# ADRF6510.net
KiCad netlist of a schematic drawn in Altium Designer
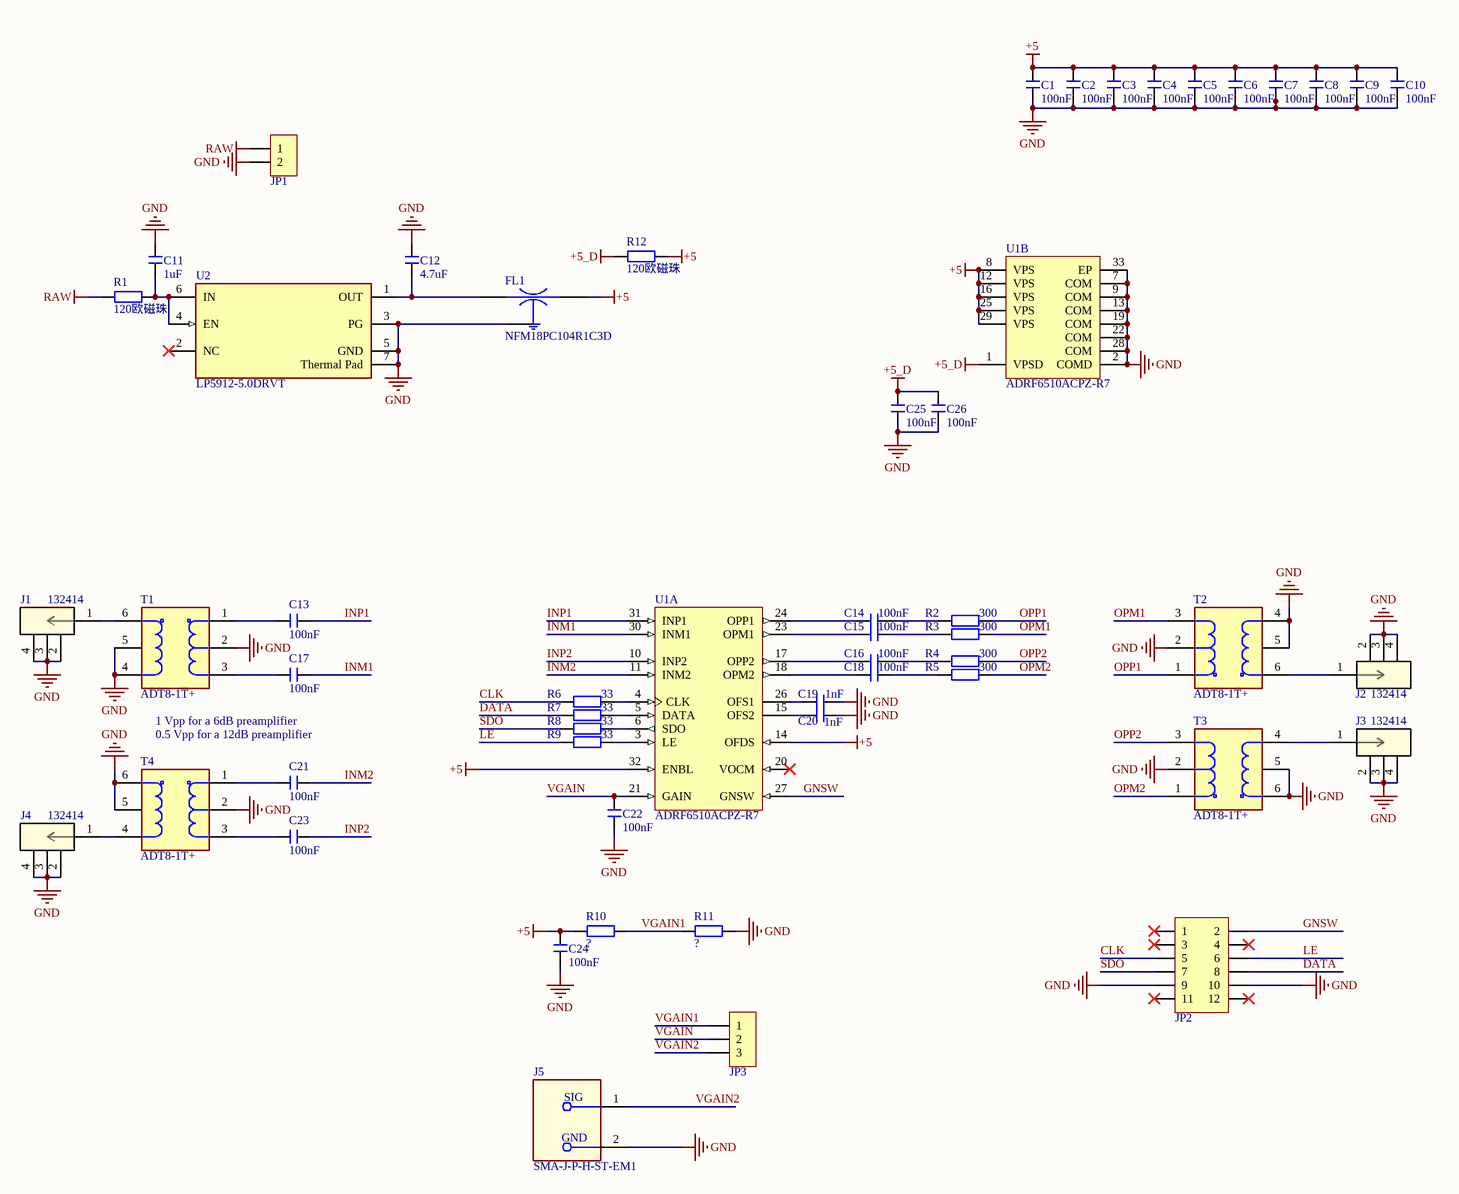
[diagram p0: ADRF6510.SchDoc]

(export (version "E")
  (design (tool "Eeschema 10.0.6"))
  (components
    (comp (ref "C1")
      (value "100nF")
      (footprint "C 0402_L")
      (description "贴片电容")
      (libsource (lib "01 - 电容-电阻-电感") (part "C"))
    )
    (comp (ref "C2")
      (value "100nF")
      (footprint "C 0402_L")
      (description "贴片电容")
      (libsource (lib "01 - 电容-电阻-电感") (part "C"))
    )
    (comp (ref "C3")
      (value "100nF")
      (footprint "C 0402_L")
      (description "贴片电容")
      (libsource (lib "01 - 电容-电阻-电感") (part "C"))
    )
    (comp (ref "C4")
      (value "100nF")
      (footprint "C 0402_L")
      (description "贴片电容")
      (libsource (lib "01 - 电容-电阻-电感") (part "C"))
    )
    (comp (ref "C5")
      (value "100nF")
      (footprint "C 0402_L")
      (description "贴片电容")
      (libsource (lib "01 - 电容-电阻-电感") (part "C"))
    )
    (comp (ref "C6")
      (value "100nF")
      (footprint "C 0402_L")
      (description "贴片电容")
      (libsource (lib "01 - 电容-电阻-电感") (part "C"))
    )
    (comp (ref "C7")
      (value "100nF")
      (footprint "C 0402_L")
      (description "贴片电容")
      (libsource (lib "01 - 电容-电阻-电感") (part "C"))
    )
    (comp (ref "C8")
      (value "100nF")
      (footprint "C 0402_L")
      (description "贴片电容")
      (libsource (lib "01 - 电容-电阻-电感") (part "C"))
    )
    (comp (ref "C9")
      (value "100nF")
      (footprint "C 0402_L")
      (description "贴片电容")
      (libsource (lib "01 - 电容-电阻-电感") (part "C"))
    )
    (comp (ref "C10")
      (value "100nF")
      (footprint "C 0402_L")
      (description "贴片电容")
      (libsource (lib "01 - 电容-电阻-电感") (part "C"))
    )
    (comp (ref "C11")
      (value "1uF")
      (footprint "C 0603_L")
      (description "贴片电容")
      (libsource (lib "01 - 电容-电阻-电感") (part "C"))
    )
    (comp (ref "C12")
      (value "4.7uF")
      (footprint "C 0603_L")
      (description "贴片电容")
      (libsource (lib "01 - 电容-电阻-电感") (part "C"))
    )
    (comp (ref "C13")
      (value "100nF")
      (footprint "C 0402_L")
      (description "贴片电容")
      (libsource (lib "01 - 电容-电阻-电感") (part "C"))
    )
    (comp (ref "C14")
      (value "100nF")
      (footprint "C 0402_L")
      (description "贴片电容")
      (libsource (lib "01 - 电容-电阻-电感") (part "C"))
    )
    (comp (ref "C15")
      (value "100nF")
      (footprint "C 0402_L")
      (description "贴片电容")
      (libsource (lib "01 - 电容-电阻-电感") (part "C"))
    )
    (comp (ref "C16")
      (value "100nF")
      (footprint "C 0402_L")
      (description "贴片电容")
      (libsource (lib "01 - 电容-电阻-电感") (part "C"))
    )
    (comp (ref "C17")
      (value "100nF")
      (footprint "C 0402_L")
      (description "贴片电容")
      (libsource (lib "01 - 电容-电阻-电感") (part "C"))
    )
    (comp (ref "C18")
      (value "100nF")
      (footprint "C 0402_L")
      (description "贴片电容")
      (libsource (lib "01 - 电容-电阻-电感") (part "C"))
    )
    (comp (ref "C19")
      (value "1nF")
      (footprint "C 0402_L")
      (description "贴片电容")
      (libsource (lib "01 - 电容-电阻-电感") (part "C"))
    )
    (comp (ref "C20")
      (value "1nF")
      (footprint "C 0402_L")
      (description "贴片电容")
      (libsource (lib "01 - 电容-电阻-电感") (part "C"))
    )
    (comp (ref "C21")
      (value "100nF")
      (footprint "C 0402_L")
      (description "贴片电容")
      (libsource (lib "01 - 电容-电阻-电感") (part "C"))
    )
    (comp (ref "C22")
      (value "100nF")
      (footprint "C 0402_L")
      (description "贴片电容")
      (libsource (lib "01 - 电容-电阻-电感") (part "C"))
    )
    (comp (ref "C23")
      (value "100nF")
      (footprint "C 0402_L")
      (description "贴片电容")
      (libsource (lib "01 - 电容-电阻-电感") (part "C"))
    )
    (comp (ref "C24")
      (value "100nF")
      (footprint "C 0402_L")
      (description "贴片电容")
      (libsource (lib "01 - 电容-电阻-电感") (part "C"))
    )
    (comp (ref "C25")
      (value "100nF")
      (footprint "C 0402_L")
      (description "贴片电容")
      (libsource (lib "01 - 电容-电阻-电感") (part "C"))
    )
    (comp (ref "C26")
      (value "100nF")
      (footprint "C 0402_L")
      (description "贴片电容")
      (libsource (lib "01 - 电容-电阻-电感") (part "C"))
    )
    (comp (ref "FL1")
      (value "NFM18PC104R1C3D")
      (footprint "FIL_NFM18PC104R1C3D")
      (description "SMD Capacitor with Capacitance: 0.10uF Tol. 20%. Rated Voltage: 16Vdc")
      (fields (field (name "MF") "Murata") (field (name "DIGI-KEY_PART_NUMBER") "490-6969-1-ND"))
      (libsource (lib "NFM18PC104R1C3D") (part "NFM18PC104R1C3D"))
    )
    (comp (ref "J1")
      (value "132414")
      (footprint "CONN_132414_AMP")
      (description "No Description Available")
      (fields (field (name "COPYRIGHT") "Copyright (C) 2022 Ultra Librarian. All rights reserved."))
      (libsource (lib "") (part "132414_1"))
    )
    (comp (ref "J2")
      (value "132414")
      (footprint "CONN_132414_AMP")
      (description "No Description Available")
      (fields (field (name "COPYRIGHT") "Copyright (C) 2022 Ultra Librarian. All rights reserved."))
      (libsource (lib "细针大偏脚SMA(用这个)") (part "132414"))
    )
    (comp (ref "J3")
      (value "132414")
      (footprint "CONN_132414_AMP")
      (description "No Description Available")
      (fields (field (name "COPYRIGHT") "Copyright (C) 2022 Ultra Librarian. All rights reserved."))
      (libsource (lib "") (part "132414_2"))
    )
    (comp (ref "J4")
      (value "132414")
      (footprint "CONN_132414_AMP")
      (description "No Description Available")
      (fields (field (name "COPYRIGHT") "Copyright (C) 2022 Ultra Librarian. All rights reserved."))
      (libsource (lib "") (part "132414_1"))
    )
    (comp (ref "J5")
      (value "SMA-J-P-H-ST-EM1")
      (footprint "FP-SMA-J-P-H-ST-EM1-MFG")
      (description "CONN SMA JACK STR 50OHM EDGE MNT")
      (libsource (lib "卧式SMA") (part "CMP-02754-000006-1"))
    )
    (comp (ref "JP1")
      (value "HDR-1X2")
      (footprint "KF2510-LI-2P")
      (description "2P接插件")
      (libsource (lib "18 - 接插件-脚距2.54mm (100mil) ") (part "Header 2"))
    )
    (comp (ref "JP2")
      (value "Header 6X2")
      (footprint "HDR2.54-WI-2x6P")
      (description "6*2P接插件")
      (libsource (lib "18 - 接插件-脚距2.54mm (100mil) ") (part "Header  6X2"))
    )
    (comp (ref "JP3")
      (value "HDR-1X3")
      (footprint "HDR2.54-LI-3P")
      (description "3P接插件")
      (libsource (lib "18 - 接插件-脚距2.54mm (100mil) ") (part "Header 3"))
    )
    (comp (ref "R1")
      (value "120欧磁珠")
      (footprint "R 0603_L")
      (description "贴片电阻")
      (libsource (lib "01 - 电容-电阻-电感") (part "R"))
    )
    (comp (ref "R2")
      (value "300")
      (footprint "R 0402_L")
      (description "贴片电阻")
      (libsource (lib "01 - 电容-电阻-电感") (part "R"))
    )
    (comp (ref "R3")
      (value "300")
      (footprint "R 0402_L")
      (description "贴片电阻")
      (libsource (lib "01 - 电容-电阻-电感") (part "R"))
    )
    (comp (ref "R4")
      (value "300")
      (footprint "R 0402_L")
      (description "贴片电阻")
      (libsource (lib "01 - 电容-电阻-电感") (part "R"))
    )
    (comp (ref "R5")
      (value "300")
      (footprint "R 0402_L")
      (description "贴片电阻")
      (libsource (lib "01 - 电容-电阻-电感") (part "R"))
    )
    (comp (ref "R6")
      (value "33")
      (footprint "R 0402_L")
      (description "贴片电阻")
      (libsource (lib "01 - 电容-电阻-电感") (part "R"))
    )
    (comp (ref "R7")
      (value "33")
      (footprint "R 0402_L")
      (description "贴片电阻")
      (libsource (lib "01 - 电容-电阻-电感") (part "R"))
    )
    (comp (ref "R8")
      (value "33")
      (footprint "R 0402_L")
      (description "贴片电阻")
      (libsource (lib "01 - 电容-电阻-电感") (part "R"))
    )
    (comp (ref "R9")
      (value "33")
      (footprint "R 0402_L")
      (description "贴片电阻")
      (libsource (lib "01 - 电容-电阻-电感") (part "R"))
    )
    (comp (ref "R10")
      (value "?")
      (footprint "R 0603_L")
      (description "贴片电阻")
      (libsource (lib "01 - 电容-电阻-电感") (part "R"))
    )
    (comp (ref "R11")
      (value "?")
      (footprint "R 0603_L")
      (description "贴片电阻")
      (libsource (lib "01 - 电容-电阻-电感") (part "R"))
    )
    (comp (ref "R12")
      (value "120欧磁珠")
      (footprint "R 0603_L")
      (description "贴片电阻")
      (libsource (lib "01 - 电容-电阻-电感") (part "R"))
    )
    (comp (ref "T1")
      (value "ADT8-1T+")
      (footprint "ADT8-1T+")
      (description "RF Transformer, 50 ohm, 8.0: 1, 0.10-130 MHz, SMT")
      (libsource (lib "") (part "CMP-00025-00008-6_1"))
    )
    (comp (ref "T2")
      (value "ADT8-1T+")
      (footprint "ADT8-1T+")
      (description "RF Transformer, 50 ohm, 8.0: 1, 0.10-130 MHz, SMT")
      (libsource (lib "ADT8-1T+") (part "CMP-00025-00008-6"))
    )
    (comp (ref "T3")
      (value "ADT8-1T+")
      (footprint "ADT8-1T+")
      (description "RF Transformer, 50 ohm, 8.0: 1, 0.10-130 MHz, SMT")
      (libsource (lib "ADT8-1T+") (part "CMP-00025-00008-6"))
    )
    (comp (ref "T4")
      (value "ADT8-1T+")
      (footprint "ADT8-1T+")
      (description "RF Transformer, 50 ohm, 8.0: 1, 0.10-130 MHz, SMT")
      (libsource (lib "") (part "CMP-00025-00008-6_1"))
    )
    (comp (ref "U1")
      (value "ADRF6510ACPZ-R7")
      (footprint "ADI-CP-32-2_N")
      (libsource (lib "ADRF6510ACPZ") (part "ADRF510ACPZ"))
    )
    (comp (ref "U2")
      (value "LP5912-5.0DRVT")
      (footprint "FP-DRV0006A-MFG")
      (description "IC REG LINEAR 500MA 6SON")
      (libsource (lib "LP5912") (part "LP5912DRVT"))
    )
  )
  (nets
    (net (code "1") (name "+5") (class "Default")
      (node (ref "C1") (pin "2") (pinfunction "2_2") (pintype "passive"))
      (node (ref "C10") (pin "2") (pinfunction "2_2") (pintype "passive"))
      (node (ref "C2") (pin "2") (pinfunction "2_2") (pintype "passive"))
      (node (ref "C24") (pin "2") (pinfunction "2_2") (pintype "passive"))
      (node (ref "C3") (pin "2") (pinfunction "2_2") (pintype "passive"))
      (node (ref "C4") (pin "2") (pinfunction "2_2") (pintype "passive"))
      (node (ref "C5") (pin "2") (pinfunction "2_2") (pintype "passive"))
      (node (ref "C6") (pin "2") (pinfunction "2_2") (pintype "passive"))
      (node (ref "C7") (pin "2") (pinfunction "2_2") (pintype "passive"))
      (node (ref "C8") (pin "2") (pinfunction "2_2") (pintype "passive"))
      (node (ref "C9") (pin "2") (pinfunction "2_2") (pintype "passive"))
      (node (ref "FL1") (pin "3") (pinfunction "OUT_3") (pintype "passive"))
      (node (ref "R10") (pin "1") (pinfunction "1_1") (pintype "passive"))
      (node (ref "R12") (pin "2") (pinfunction "2_2") (pintype "passive"))
      (node (ref "U1") (pin "12") (pinfunction "VPS_12") (pintype "power_in"))
      (node (ref "U1") (pin "14") (pinfunction "OFDS_14") (pintype "input"))
      (node (ref "U1") (pin "16") (pinfunction "VPS_16") (pintype "power_in"))
      (node (ref "U1") (pin "25") (pinfunction "VPS_25") (pintype "power_in"))
      (node (ref "U1") (pin "29") (pinfunction "VPS_29") (pintype "power_in"))
      (node (ref "U1") (pin "32") (pinfunction "ENBL_32") (pintype "input"))
      (node (ref "U1") (pin "8") (pinfunction "VPS_8") (pintype "power_in"))
    )
    (net (code "2") (name "+5_D") (class "Default")
      (node (ref "C25") (pin "2") (pinfunction "2_2") (pintype "passive"))
      (node (ref "C26") (pin "2") (pinfunction "2_2") (pintype "passive"))
      (node (ref "R12") (pin "1") (pinfunction "1_1") (pintype "passive"))
      (node (ref "U1") (pin "1") (pinfunction "VPSD_1") (pintype "power_in"))
    )
    (net (code "3") (name "/CLK") (class "Default")
      (node (ref "JP2") (pin "5") (pinfunction "5_5") (pintype "passive"))
      (node (ref "R6") (pin "1") (pinfunction "1_1") (pintype "passive"))
    )
    (net (code "4") (name "/DATA") (class "Default")
      (node (ref "JP2") (pin "8") (pinfunction "8_8") (pintype "passive"))
      (node (ref "R7") (pin "1") (pinfunction "1_1") (pintype "passive"))
    )
    (net (code "5") (name "/GNSW") (class "Default")
      (node (ref "JP2") (pin "2") (pinfunction "2_2") (pintype "passive"))
      (node (ref "U1") (pin "27") (pinfunction "GNSW_27") (pintype "input"))
    )
    (net (code "6") (name "/INM1") (class "Default")
      (node (ref "C17") (pin "1") (pinfunction "1_1") (pintype "passive"))
      (node (ref "U1") (pin "30") (pinfunction "INM1_30") (pintype "input"))
    )
    (net (code "7") (name "/INM2") (class "Default")
      (node (ref "C21") (pin "1") (pinfunction "1_1") (pintype "passive"))
      (node (ref "U1") (pin "11") (pinfunction "INM2_11") (pintype "input"))
    )
    (net (code "8") (name "/INP1") (class "Default")
      (node (ref "C13") (pin "1") (pinfunction "1_1") (pintype "passive"))
      (node (ref "U1") (pin "31") (pinfunction "INP1_31") (pintype "input"))
    )
    (net (code "9") (name "/INP2") (class "Default")
      (node (ref "C23") (pin "1") (pinfunction "1_1") (pintype "passive"))
      (node (ref "U1") (pin "10") (pinfunction "INP2_10") (pintype "input"))
    )
    (net (code "10") (name "/LE") (class "Default")
      (node (ref "JP2") (pin "6") (pinfunction "6_6") (pintype "passive"))
      (node (ref "R9") (pin "1") (pinfunction "1_1") (pintype "passive"))
    )
    (net (code "11") (name "/OPM1") (class "Default")
      (node (ref "R3") (pin "2") (pinfunction "2_2") (pintype "passive"))
      (node (ref "T2") (pin "3") (pinfunction "SECONDARY_MID_3") (pintype "passive"))
    )
    (net (code "12") (name "/OPM2") (class "Default")
      (node (ref "R5") (pin "2") (pinfunction "2_2") (pintype "passive"))
      (node (ref "T3") (pin "1") (pinfunction "SECONDARY_DOT_1") (pintype "passive"))
    )
    (net (code "13") (name "/OPP1") (class "Default")
      (node (ref "R2") (pin "2") (pinfunction "2_2") (pintype "passive"))
      (node (ref "T2") (pin "1") (pinfunction "SECONDARY_DOT_1") (pintype "passive"))
    )
    (net (code "14") (name "/OPP2") (class "Default")
      (node (ref "R4") (pin "2") (pinfunction "2_2") (pintype "passive"))
      (node (ref "T3") (pin "3") (pinfunction "SECONDARY_MID_3") (pintype "passive"))
    )
    (net (code "15") (name "/SDO") (class "Default")
      (node (ref "JP2") (pin "7") (pinfunction "7_7") (pintype "passive"))
      (node (ref "R8") (pin "1") (pinfunction "1_1") (pintype "passive"))
    )
    (net (code "16") (name "/VGAIN") (class "Default")
      (node (ref "C22") (pin "2") (pinfunction "2_2") (pintype "passive"))
      (node (ref "JP3") (pin "2") (pinfunction "2_2") (pintype "passive"))
      (node (ref "U1") (pin "21") (pinfunction "GAIN_21") (pintype "input"))
    )
    (net (code "17") (name "/VGAIN1") (class "Default")
      (node (ref "JP3") (pin "1") (pinfunction "1_1") (pintype "passive"))
      (node (ref "R10") (pin "2") (pinfunction "2_2") (pintype "passive"))
      (node (ref "R11") (pin "1") (pinfunction "1_1") (pintype "passive"))
    )
    (net (code "18") (name "/VGAIN2") (class "Default")
      (node (ref "J5") (pin "1") (pinfunction "1_1") (pintype "passive"))
      (node (ref "JP3") (pin "3") (pinfunction "3_3") (pintype "passive"))
    )
    (net (code "19") (name "GND") (class "Default")
      (node (ref "C1") (pin "1") (pinfunction "1_1") (pintype "passive"))
      (node (ref "C10") (pin "1") (pinfunction "1_1") (pintype "passive"))
      (node (ref "C11") (pin "2") (pinfunction "2_2") (pintype "passive"))
      (node (ref "C12") (pin "2") (pinfunction "2_2") (pintype "passive"))
      (node (ref "C19") (pin "2") (pinfunction "2_2") (pintype "passive"))
      (node (ref "C2") (pin "1") (pinfunction "1_1") (pintype "passive"))
      (node (ref "C20") (pin "2") (pinfunction "2_2") (pintype "passive"))
      (node (ref "C22") (pin "1") (pinfunction "1_1") (pintype "passive"))
      (node (ref "C24") (pin "1") (pinfunction "1_1") (pintype "passive"))
      (node (ref "C25") (pin "1") (pinfunction "1_1") (pintype "passive"))
      (node (ref "C26") (pin "1") (pinfunction "1_1") (pintype "passive"))
      (node (ref "C3") (pin "1") (pinfunction "1_1") (pintype "passive"))
      (node (ref "C4") (pin "1") (pinfunction "1_1") (pintype "passive"))
      (node (ref "C5") (pin "1") (pinfunction "1_1") (pintype "passive"))
      (node (ref "C6") (pin "1") (pinfunction "1_1") (pintype "passive"))
      (node (ref "C7") (pin "1") (pinfunction "1_1") (pintype "passive"))
      (node (ref "C8") (pin "1") (pinfunction "1_1") (pintype "passive"))
      (node (ref "C9") (pin "1") (pinfunction "1_1") (pintype "passive"))
      (node (ref "FL1") (pin "2") (pinfunction "GND_2") (pintype "power_in"))
      (node (ref "J1") (pin "2") (pinfunction "2_2") (pintype "passive"))
      (node (ref "J1") (pin "3") (pinfunction "3_3") (pintype "passive"))
      (node (ref "J1") (pin "4") (pinfunction "4_4") (pintype "passive"))
      (node (ref "J2") (pin "2") (pinfunction "2_2") (pintype "passive"))
      (node (ref "J2") (pin "3") (pinfunction "3_3") (pintype "passive"))
      (node (ref "J2") (pin "4") (pinfunction "4_4") (pintype "passive"))
      (node (ref "J3") (pin "2") (pinfunction "2_2") (pintype "passive"))
      (node (ref "J3") (pin "3") (pinfunction "3_3") (pintype "passive"))
      (node (ref "J3") (pin "4") (pinfunction "4_4") (pintype "passive"))
      (node (ref "J4") (pin "2") (pinfunction "2_2") (pintype "passive"))
      (node (ref "J4") (pin "3") (pinfunction "3_3") (pintype "passive"))
      (node (ref "J4") (pin "4") (pinfunction "4_4") (pintype "passive"))
      (node (ref "J5") (pin "2") (pinfunction "MNT_1_2") (pintype "passive"))
      (node (ref "JP1") (pin "2") (pinfunction "2_2") (pintype "passive"))
      (node (ref "JP2") (pin "10") (pinfunction "10_10") (pintype "passive"))
      (node (ref "JP2") (pin "9") (pinfunction "9_9") (pintype "passive"))
      (node (ref "R11") (pin "2") (pinfunction "2_2") (pintype "passive"))
      (node (ref "T1") (pin "2") (pinfunction "SECONDARY_2") (pintype "passive"))
      (node (ref "T1") (pin "4") (pinfunction "PRIMARY_4") (pintype "passive"))
      (node (ref "T1") (pin "5") (pinfunction "NC_5") (pintype "passive"))
      (node (ref "T2") (pin "2") (pinfunction "SECONDARY_2") (pintype "passive"))
      (node (ref "T2") (pin "4") (pinfunction "PRIMARY_4") (pintype "passive"))
      (node (ref "T2") (pin "5") (pinfunction "NC_5") (pintype "passive"))
      (node (ref "T3") (pin "2") (pinfunction "SECONDARY_2") (pintype "passive"))
      (node (ref "T3") (pin "5") (pinfunction "NC_5") (pintype "passive"))
      (node (ref "T3") (pin "6") (pinfunction "PRIMARY_DOT_6") (pintype "passive"))
      (node (ref "T4") (pin "2") (pinfunction "SECONDARY_2") (pintype "passive"))
      (node (ref "T4") (pin "5") (pinfunction "NC_5") (pintype "passive"))
      (node (ref "T4") (pin "6") (pinfunction "PRIMARY_DOT_6") (pintype "passive"))
      (node (ref "U1") (pin "13") (pinfunction "COM_13") (pintype "power_in"))
      (node (ref "U1") (pin "19") (pinfunction "COM_19") (pintype "power_in"))
      (node (ref "U1") (pin "2") (pinfunction "COMD_2") (pintype "power_in"))
      (node (ref "U1") (pin "22") (pinfunction "COM_22") (pintype "power_in"))
      (node (ref "U1") (pin "28") (pinfunction "COM_28") (pintype "power_in"))
      (node (ref "U1") (pin "33") (pinfunction "EP_33") (pintype "power_in"))
      (node (ref "U1") (pin "7") (pinfunction "COM_7") (pintype "power_in"))
      (node (ref "U1") (pin "9") (pinfunction "COM_9") (pintype "power_in"))
      (node (ref "U2") (pin "3") (pinfunction "PG_3") (pintype "open_collector"))
      (node (ref "U2") (pin "5") (pinfunction "GND_5") (pintype "power_in"))
      (node (ref "U2") (pin "7") (pinfunction "Thermal_Pad_7") (pintype "power_in"))
    )
    (net (code "20") (name "Net-(C14-Pad2)") (class "Default")
      (node (ref "C14") (pin "2") (pinfunction "2_2") (pintype "passive"))
      (node (ref "R2") (pin "1") (pinfunction "1_1") (pintype "passive"))
    )
    (net (code "21") (name "Net-(C15-Pad2)") (class "Default")
      (node (ref "C15") (pin "2") (pinfunction "2_2") (pintype "passive"))
      (node (ref "R3") (pin "1") (pinfunction "1_1") (pintype "passive"))
    )
    (net (code "22") (name "Net-(C16-Pad2)") (class "Default")
      (node (ref "C16") (pin "2") (pinfunction "2_2") (pintype "passive"))
      (node (ref "R4") (pin "1") (pinfunction "1_1") (pintype "passive"))
    )
    (net (code "23") (name "Net-(C18-Pad2)") (class "Default")
      (node (ref "C18") (pin "2") (pinfunction "2_2") (pintype "passive"))
      (node (ref "R5") (pin "1") (pinfunction "1_1") (pintype "passive"))
    )
    (net (code "24") (name "Net-(FL1-IN)") (class "Default")
      (node (ref "C12") (pin "1") (pinfunction "1_1") (pintype "passive"))
      (node (ref "FL1") (pin "1") (pinfunction "IN_1") (pintype "passive"))
      (node (ref "U2") (pin "1") (pinfunction "OUT_1") (pintype "power_in"))
    )
    (net (code "25") (name "Net-(T1-PRIMARY_DOT)") (class "Default")
      (node (ref "J1") (pin "1") (pinfunction "1_1") (pintype "passive"))
      (node (ref "T1") (pin "6") (pinfunction "PRIMARY_DOT_6") (pintype "passive"))
    )
    (net (code "26") (name "Net-(T1-SECONDARY_DOT)") (class "Default")
      (node (ref "C13") (pin "2") (pinfunction "2_2") (pintype "passive"))
      (node (ref "T1") (pin "1") (pinfunction "SECONDARY_DOT_1") (pintype "passive"))
    )
    (net (code "27") (name "Net-(T1-SECONDARY_MID)") (class "Default")
      (node (ref "C17") (pin "2") (pinfunction "2_2") (pintype "passive"))
      (node (ref "T1") (pin "3") (pinfunction "SECONDARY_MID_3") (pintype "passive"))
    )
    (net (code "28") (name "Net-(T2-PRIMARY_DOT)") (class "Default")
      (node (ref "J2") (pin "1") (pinfunction "1_1") (pintype "passive"))
      (node (ref "T2") (pin "6") (pinfunction "PRIMARY_DOT_6") (pintype "passive"))
    )
    (net (code "29") (name "Net-(T3-PRIMARY)") (class "Default")
      (node (ref "J3") (pin "1") (pinfunction "1_1") (pintype "passive"))
      (node (ref "T3") (pin "4") (pinfunction "PRIMARY_4") (pintype "passive"))
    )
    (net (code "30") (name "Net-(T4-PRIMARY)") (class "Default")
      (node (ref "J4") (pin "1") (pinfunction "1_1") (pintype "passive"))
      (node (ref "T4") (pin "4") (pinfunction "PRIMARY_4") (pintype "passive"))
    )
    (net (code "31") (name "Net-(T4-SECONDARY_DOT)") (class "Default")
      (node (ref "C21") (pin "2") (pinfunction "2_2") (pintype "passive"))
      (node (ref "T4") (pin "1") (pinfunction "SECONDARY_DOT_1") (pintype "passive"))
    )
    (net (code "32") (name "Net-(T4-SECONDARY_MID)") (class "Default")
      (node (ref "C23") (pin "2") (pinfunction "2_2") (pintype "passive"))
      (node (ref "T4") (pin "3") (pinfunction "SECONDARY_MID_3") (pintype "passive"))
    )
    (net (code "33") (name "Net-(U1A-CLK)") (class "Default")
      (node (ref "R6") (pin "2") (pinfunction "2_2") (pintype "passive"))
      (node (ref "U1") (pin "4") (pinfunction "CLK_4") (pintype "input"))
    )
    (net (code "34") (name "Net-(U1A-DATA)") (class "Default")
      (node (ref "R7") (pin "2") (pinfunction "2_2") (pintype "passive"))
      (node (ref "U1") (pin "5") (pinfunction "DATA_5") (pintype "input"))
    )
    (net (code "35") (name "Net-(U1A-LE)") (class "Default")
      (node (ref "R9") (pin "2") (pinfunction "2_2") (pintype "passive"))
      (node (ref "U1") (pin "3") (pinfunction "LE_3") (pintype "input"))
    )
    (net (code "36") (name "Net-(U1A-OFS1)") (class "Default")
      (node (ref "C19") (pin "1") (pinfunction "1_1") (pintype "passive"))
      (node (ref "U1") (pin "26") (pinfunction "OFS1_26") (pintype "passive"))
    )
    (net (code "37") (name "Net-(U1A-OFS2)") (class "Default")
      (node (ref "C20") (pin "1") (pinfunction "1_1") (pintype "passive"))
      (node (ref "U1") (pin "15") (pinfunction "OFS2_15") (pintype "passive"))
    )
    (net (code "38") (name "Net-(U1A-OPM1)") (class "Default")
      (node (ref "C15") (pin "1") (pinfunction "1_1") (pintype "passive"))
      (node (ref "U1") (pin "23") (pinfunction "OPM1_23") (pintype "output"))
    )
    (net (code "39") (name "Net-(U1A-OPM2)") (class "Default")
      (node (ref "C18") (pin "1") (pinfunction "1_1") (pintype "passive"))
      (node (ref "U1") (pin "18") (pinfunction "OPM2_18") (pintype "output"))
    )
    (net (code "40") (name "Net-(U1A-OPP1)") (class "Default")
      (node (ref "C14") (pin "1") (pinfunction "1_1") (pintype "passive"))
      (node (ref "U1") (pin "24") (pinfunction "OPP1_24") (pintype "output"))
    )
    (net (code "41") (name "Net-(U1A-OPP2)") (class "Default")
      (node (ref "C16") (pin "1") (pinfunction "1_1") (pintype "passive"))
      (node (ref "U1") (pin "17") (pinfunction "OPP2_17") (pintype "output"))
    )
    (net (code "42") (name "Net-(U1A-SDO)") (class "Default")
      (node (ref "R8") (pin "2") (pinfunction "2_2") (pintype "passive"))
      (node (ref "U1") (pin "6") (pinfunction "SDO_6") (pintype "output"))
    )
    (net (code "43") (name "Net-(U2-EN)") (class "Default")
      (node (ref "C11") (pin "1") (pinfunction "1_1") (pintype "passive"))
      (node (ref "R1") (pin "2") (pinfunction "2_2") (pintype "passive"))
      (node (ref "U2") (pin "4") (pinfunction "EN_4") (pintype "input"))
      (node (ref "U2") (pin "6") (pinfunction "IN_6") (pintype "power_in"))
    )
    (net (code "44") (name "RAW") (class "Default")
      (node (ref "JP1") (pin "1") (pinfunction "1_1") (pintype "passive"))
      (node (ref "R1") (pin "1") (pinfunction "1_1") (pintype "passive"))
    )
    (net (code "45") (name "unconnected-(JP2-Pad1)") (class "Default")
      (node (ref "JP2") (pin "1") (pinfunction "1_1") (pintype "passive+no_connect"))
    )
    (net (code "46") (name "unconnected-(JP2-Pad3)") (class "Default")
      (node (ref "JP2") (pin "3") (pinfunction "3_3") (pintype "passive+no_connect"))
    )
    (net (code "47") (name "unconnected-(JP2-Pad4)") (class "Default")
      (node (ref "JP2") (pin "4") (pinfunction "4_4") (pintype "passive+no_connect"))
    )
    (net (code "48") (name "unconnected-(JP2-Pad11)") (class "Default")
      (node (ref "JP2") (pin "11") (pinfunction "11_11") (pintype "passive+no_connect"))
    )
    (net (code "49") (name "unconnected-(JP2-Pad12)") (class "Default")
      (node (ref "JP2") (pin "12") (pinfunction "12_12") (pintype "passive+no_connect"))
    )
    (net (code "50") (name "unconnected-(U1A-VOCM-Pad20)") (class "Default")
      (node (ref "U1") (pin "20") (pinfunction "VOCM_20") (pintype "input+no_connect"))
    )
    (net (code "51") (name "unconnected-(U2-NC-Pad2)") (class "Default")
      (node (ref "U2") (pin "2") (pinfunction "NC_2") (pintype "passive+no_connect"))
    )
  )
)
